# powerStage.net
KiCad netlist of a schematic drawn in Altium Designer
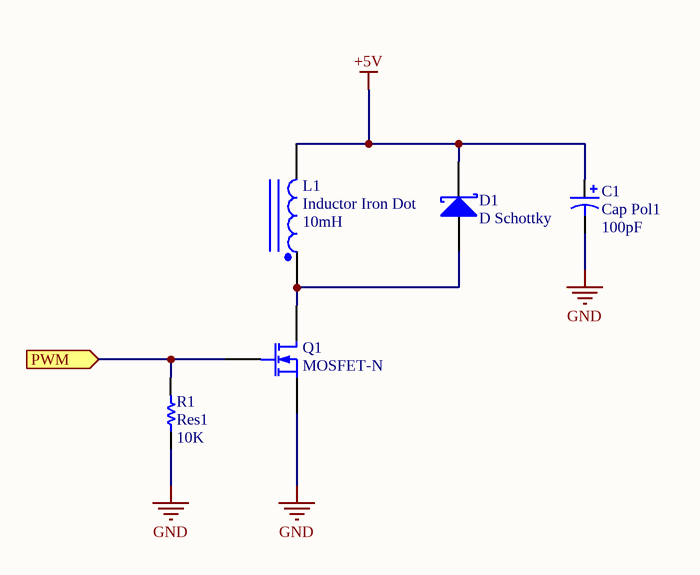
[diagram p0: powerStage.SchDoc]

(export (version "E")
  (design (tool "Eeschema 10.0.6"))
  (components
    (comp (ref "C1")
      (value "Cap Pol1")
      (footprint "RB7.6-15")
      (description "Polarized Capacitor (Radial)")
      (fields (field (name "ALTIUM_VALUE") "100pF") (field (name "PUBLISHER") "Altium Limited"))
      (libsource (lib "Miscellaneous Devices") (part "Cap Pol1"))
    )
    (comp (ref "D1")
      (value "D Schottky")
      (footprint "SMB")
      (description "Schottky Diode")
      (fields (field (name "PUBLISHER") "Altium Limited"))
      (libsource (lib "Miscellaneous Devices") (part "D Schottky"))
    )
    (comp (ref "L1")
      (value "Inductor Iron Dot")
      (footprint "DIODE_SMC")
      (description "Magnetic-Core Inductor with Winding Polarity Marking")
      (fields (field (name "ALTIUM_VALUE") "10mH") (field (name "PUBLISHER") "Altium Limited"))
      (libsource (lib "Miscellaneous Devices") (part "Inductor Iron Dot"))
    )
    (comp (ref "Q1")
      (value "MOSFET-N")
      (footprint "E3")
      (description "N-Channel MOSFET")
      (fields (field (name "PUBLISHER") "Altium Limited"))
      (libsource (lib "Miscellaneous Devices") (part "MOSFET-N"))
    )
    (comp (ref "R1")
      (value "Res1")
      (footprint "AXIAL-0.3")
      (description "Resistor")
      (fields (field (name "ALTIUM_VALUE") "10K") (field (name "PUBLISHER") "Altium Limited"))
      (libsource (lib "Miscellaneous Devices") (part "Res1"))
    )
  )
  (nets
    (net (code "1") (name "+5V") (class "Default")
      (node (ref "C1") (pin "1") (pinfunction "1_1") (pintype "passive"))
      (node (ref "D1") (pin "2") (pinfunction "K_2") (pintype "passive"))
      (node (ref "L1") (pin "2") (pinfunction "2_2") (pintype "passive"))
    )
    (net (code "2") (name "/PWM") (class "Default")
      (node (ref "Q1") (pin "2") (pinfunction "G_2") (pintype "passive"))
      (node (ref "R1") (pin "2") (pinfunction "2_2") (pintype "passive"))
    )
    (net (code "3") (name "GND") (class "Default")
      (node (ref "C1") (pin "2") (pinfunction "2_2") (pintype "passive"))
      (node (ref "Q1") (pin "3") (pinfunction "S_3") (pintype "passive"))
      (node (ref "R1") (pin "1") (pinfunction "1_1") (pintype "passive"))
    )
    (net (code "4") (name "Net-(D1-A)") (class "Default")
      (node (ref "D1") (pin "1") (pinfunction "A_1") (pintype "passive"))
      (node (ref "L1") (pin "1") (pinfunction "1_1") (pintype "passive"))
      (node (ref "Q1") (pin "1") (pinfunction "D_1") (pintype "passive"))
    )
  )
)
